# Punto_DC.net
KiCad netlist of a schematic drawn in Altium Designer
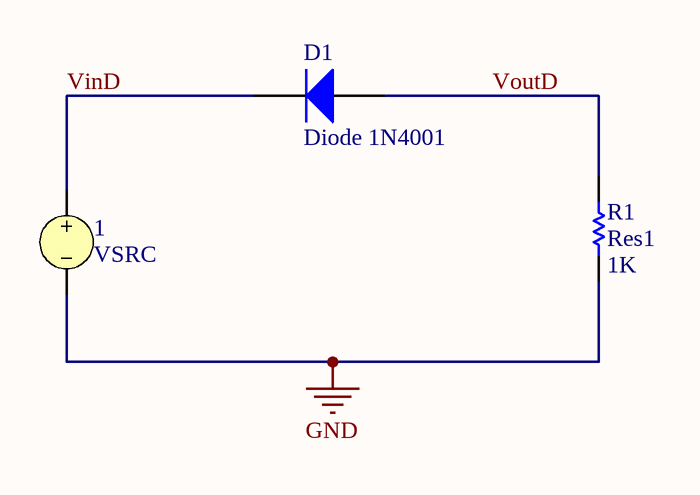
[diagram p0: Punto DC.SchDoc]

(export (version "E")
  (design (tool "Eeschema 10.0.6"))
  (components
    (comp (ref "1")
      (value "VSRC")
      (description "Voltage Source")
      (fields (field (name "PUBLISHER") "Altium Limited"))
      (libsource (lib "Simulation Sources") (part "VSRC"))
    )
    (comp (ref "D1")
      (value "Diode 1N4001")
      (footprint "DO-41")
      (description "1 Amp General Purpose Rectifier")
      (fields (field (name "PUBLISHER") "Altium Limited"))
      (libsource (lib "Miscellaneous Devices") (part "Diode 1N4001"))
    )
    (comp (ref "R1")
      (value "Res1")
      (footprint "AXIAL-0.3")
      (description "Resistor")
      (fields (field (name "ALTIUM_VALUE") "1K") (field (name "PUBLISHER") "Altium Limited"))
      (libsource (lib "Miscellaneous Devices") (part "Res1"))
    )
  )
  (nets
    (net (code "1") (name "/VinD") (class "Default")
      (node (ref "1") (pin "1") (pinfunction "1_1") (pintype "passive"))
      (node (ref "D1") (pin "2") (pinfunction "K_2") (pintype "passive"))
    )
    (net (code "2") (name "/VoutD") (class "Default")
      (node (ref "D1") (pin "1") (pinfunction "A_1") (pintype "passive"))
      (node (ref "R1") (pin "2") (pinfunction "2_2") (pintype "passive"))
    )
    (net (code "3") (name "GND") (class "Default")
      (node (ref "1") (pin "2") (pinfunction "2_2") (pintype "passive"))
      (node (ref "R1") (pin "1") (pinfunction "1_1") (pintype "passive"))
    )
  )
)
